# POV.net
KiCad netlist of a schematic drawn in EAGLE
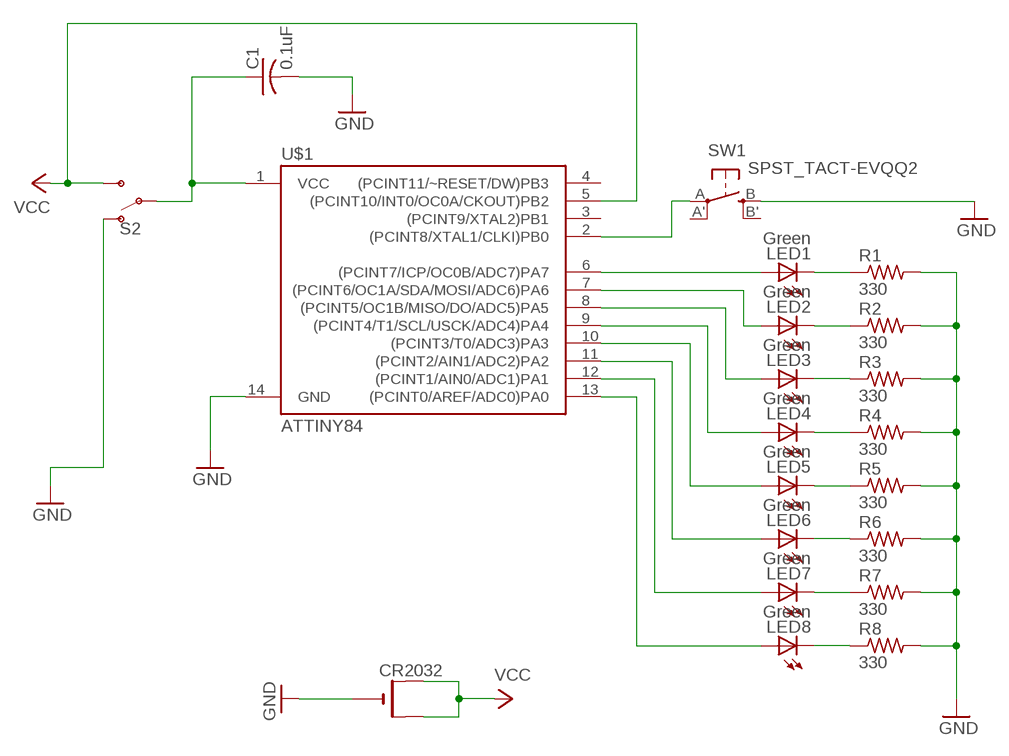
[diagram p0: schematic, sheet 1]

(export (version "E")
  (design (tool "Eeschema 10.0.6"))
  (components
    (comp (ref "C1")
      (value "0.1uF")
      (footprint "eagle-import:C0805")
      (libsource (lib "eagle-import") (part "C-USC0805"))
    )
    (comp (ref "CR2032")
      (value "CR2032SMT")
      (footprint "eagle-import:CR2032-SMD")
      (libsource (lib "eagle-import") (part "CR2032SMT"))
    )
    (comp (ref "LED1")
      (value "Green")
      (footprint "eagle-import:CHIP-LED0805")
      (libsource (lib "eagle-import") (part "LEDCHIP-LED0805"))
    )
    (comp (ref "LED2")
      (value "Green")
      (footprint "eagle-import:CHIP-LED0805")
      (libsource (lib "eagle-import") (part "LEDCHIP-LED0805"))
    )
    (comp (ref "LED3")
      (value "Green")
      (footprint "eagle-import:CHIP-LED0805")
      (libsource (lib "eagle-import") (part "LEDCHIP-LED0805"))
    )
    (comp (ref "LED4")
      (value "Green")
      (footprint "eagle-import:CHIP-LED0805")
      (libsource (lib "eagle-import") (part "LEDCHIP-LED0805"))
    )
    (comp (ref "LED5")
      (value "Green")
      (footprint "eagle-import:CHIP-LED0805")
      (libsource (lib "eagle-import") (part "LEDCHIP-LED0805"))
    )
    (comp (ref "LED6")
      (value "Green")
      (footprint "eagle-import:CHIP-LED0805")
      (libsource (lib "eagle-import") (part "LEDCHIP-LED0805"))
    )
    (comp (ref "LED7")
      (value "Green")
      (footprint "eagle-import:CHIP-LED0805")
      (libsource (lib "eagle-import") (part "LEDCHIP-LED0805"))
    )
    (comp (ref "LED8")
      (value "Green")
      (footprint "eagle-import:CHIP-LED0805")
      (libsource (lib "eagle-import") (part "LEDCHIP-LED0805"))
    )
    (comp (ref "R1")
      (value "330")
      (footprint "eagle-import:M0805")
      (libsource (lib "eagle-import") (part "R-US_M0805"))
    )
    (comp (ref "R2")
      (value "330")
      (footprint "eagle-import:M0805")
      (libsource (lib "eagle-import") (part "R-US_M0805"))
    )
    (comp (ref "R3")
      (value "330")
      (footprint "eagle-import:M0805")
      (libsource (lib "eagle-import") (part "R-US_M0805"))
    )
    (comp (ref "R4")
      (value "330")
      (footprint "eagle-import:M0805")
      (libsource (lib "eagle-import") (part "R-US_M0805"))
    )
    (comp (ref "R5")
      (value "330")
      (footprint "eagle-import:M0805")
      (libsource (lib "eagle-import") (part "R-US_M0805"))
    )
    (comp (ref "R6")
      (value "330")
      (footprint "eagle-import:M0805")
      (libsource (lib "eagle-import") (part "R-US_M0805"))
    )
    (comp (ref "R7")
      (value "330")
      (footprint "eagle-import:M0805")
      (libsource (lib "eagle-import") (part "R-US_M0805"))
    )
    (comp (ref "R8")
      (value "330")
      (footprint "eagle-import:M0805")
      (libsource (lib "eagle-import") (part "R-US_M0805"))
    )
    (comp (ref "S2")
      (value "SWITCH-SPDT-SMD-AYZ0202")
      (footprint "eagle-import:SWITCH_DPDT_SMD_AYZ0202")
      (libsource (lib "eagle-import") (part "SWITCH-SPDT-SMD-AYZ0202"))
    )
    (comp (ref "SW1")
      (value "SPST_TACT-EVQQ2")
      (footprint "eagle-import:EVQ-Q2")
      (libsource (lib "eagle-import") (part "SPST_TACT-EVQQ2"))
    )
    (comp (ref "U$1")
      (value "ATTINY84")
      (footprint "eagle-import:SO14")
      (libsource (lib "eagle-import") (part "ATTINY84"))
    )
  )
  (nets
    (net (code "1") (name "GND") (class "Default")
      (node (ref "C1") (pin "2") (pinfunction "2_2") (pintype "passive"))
      (node (ref "CR2032") (pin "-") (pinfunction "-_-") (pintype "passive"))
      (node (ref "R1") (pin "2") (pinfunction "2_2") (pintype "passive"))
      (node (ref "R2") (pin "2") (pinfunction "2_2") (pintype "passive"))
      (node (ref "R3") (pin "2") (pinfunction "2_2") (pintype "passive"))
      (node (ref "R4") (pin "2") (pinfunction "2_2") (pintype "passive"))
      (node (ref "R5") (pin "2") (pinfunction "2_2") (pintype "passive"))
      (node (ref "R6") (pin "2") (pinfunction "2_2") (pintype "passive"))
      (node (ref "R7") (pin "2") (pinfunction "2_2") (pintype "passive"))
      (node (ref "R8") (pin "2") (pinfunction "2_2") (pintype "passive"))
      (node (ref "S2") (pin "1") (pinfunction "O_1") (pintype "passive"))
      (node (ref "SW1") (pin "B") (pinfunction "S_B") (pintype "passive"))
      (node (ref "U$1") (pin "14") (pinfunction "GND_14") (pintype "bidirectional"))
    )
    (net (code "2") (name "Net-(LED1-PadC)") (class "Default")
      (node (ref "LED1") (pin "C") (pinfunction "C_C") (pintype "passive"))
      (node (ref "R1") (pin "1") (pinfunction "1_1") (pintype "passive"))
    )
    (net (code "3") (name "Net-(LED2-PadC)") (class "Default")
      (node (ref "LED2") (pin "C") (pinfunction "C_C") (pintype "passive"))
      (node (ref "R2") (pin "1") (pinfunction "1_1") (pintype "passive"))
    )
    (net (code "4") (name "Net-(LED3-PadC)") (class "Default")
      (node (ref "LED3") (pin "C") (pinfunction "C_C") (pintype "passive"))
      (node (ref "R3") (pin "1") (pinfunction "1_1") (pintype "passive"))
    )
    (net (code "5") (name "Net-(LED4-PadC)") (class "Default")
      (node (ref "LED4") (pin "C") (pinfunction "C_C") (pintype "passive"))
      (node (ref "R4") (pin "1") (pinfunction "1_1") (pintype "passive"))
    )
    (net (code "6") (name "Net-(LED5-PadC)") (class "Default")
      (node (ref "LED5") (pin "C") (pinfunction "C_C") (pintype "passive"))
      (node (ref "R5") (pin "1") (pinfunction "1_1") (pintype "passive"))
    )
    (net (code "7") (name "Net-(LED6-PadC)") (class "Default")
      (node (ref "LED6") (pin "C") (pinfunction "C_C") (pintype "passive"))
      (node (ref "R6") (pin "1") (pinfunction "1_1") (pintype "passive"))
    )
    (net (code "8") (name "Net-(LED7-PadC)") (class "Default")
      (node (ref "LED7") (pin "C") (pinfunction "C_C") (pintype "passive"))
      (node (ref "R7") (pin "1") (pinfunction "1_1") (pintype "passive"))
    )
    (net (code "9") (name "Net-(LED8-PadC)") (class "Default")
      (node (ref "LED8") (pin "C") (pinfunction "C_C") (pintype "passive"))
      (node (ref "R8") (pin "1") (pinfunction "1_1") (pintype "passive"))
    )
    (net (code "10") (name "Net-(S2-P)") (class "Default")
      (node (ref "C1") (pin "1") (pinfunction "1_1") (pintype "passive"))
      (node (ref "S2") (pin "2") (pinfunction "P_2") (pintype "passive"))
      (node (ref "U$1") (pin "1") (pinfunction "VCC_1") (pintype "bidirectional"))
    )
    (net (code "11") (name "Net-(SW1-P)") (class "Default")
      (node (ref "SW1") (pin "A") (pinfunction "P_A") (pintype "passive"))
      (node (ref "U$1") (pin "2") (pinfunction "(PCINT8/XTAL1/CLKI)PB0_2") (pintype "bidirectional"))
    )
    (net (code "12") (name "Net-(U$1-(PCINT0{slash}AREF{slash}ADC0)PA0)") (class "Default")
      (node (ref "LED8") (pin "A") (pinfunction "A_A") (pintype "passive"))
      (node (ref "U$1") (pin "13") (pinfunction "(PCINT0/AREF/ADC0)PA0_13") (pintype "bidirectional"))
    )
    (net (code "13") (name "Net-(U$1-(PCINT1{slash}AIN0{slash}ADC1)PA1)") (class "Default")
      (node (ref "LED7") (pin "A") (pinfunction "A_A") (pintype "passive"))
      (node (ref "U$1") (pin "12") (pinfunction "(PCINT1/AIN0/ADC1)PA1_12") (pintype "bidirectional"))
    )
    (net (code "14") (name "Net-(U$1-(PCINT2{slash}AIN1{slash}ADC2)PA2)") (class "Default")
      (node (ref "LED6") (pin "A") (pinfunction "A_A") (pintype "passive"))
      (node (ref "U$1") (pin "11") (pinfunction "(PCINT2/AIN1/ADC2)PA2_11") (pintype "bidirectional"))
    )
    (net (code "15") (name "Net-(U$1-(PCINT3{slash}T0{slash}ADC3)PA3)") (class "Default")
      (node (ref "LED5") (pin "A") (pinfunction "A_A") (pintype "passive"))
      (node (ref "U$1") (pin "10") (pinfunction "(PCINT3/T0/ADC3)PA3_10") (pintype "bidirectional"))
    )
    (net (code "16") (name "Net-(U$1-(PCINT4{slash}T1{slash}SCL{slash}USCK{slash}ADC4)PA4)") (class "Default")
      (node (ref "LED4") (pin "A") (pinfunction "A_A") (pintype "passive"))
      (node (ref "U$1") (pin "9") (pinfunction "(PCINT4/T1/SCL/USCK/ADC4)PA4_9") (pintype "bidirectional"))
    )
    (net (code "17") (name "Net-(U$1-(PCINT5{slash}OC1B{slash}MISO{slash}DO{slash}ADC5)PA5)") (class "Default")
      (node (ref "LED3") (pin "A") (pinfunction "A_A") (pintype "passive"))
      (node (ref "U$1") (pin "8") (pinfunction "(PCINT5/OC1B/MISO/DO/ADC5)PA5_8") (pintype "bidirectional"))
    )
    (net (code "18") (name "Net-(U$1-(PCINT6{slash}OC1A{slash}SDA{slash}MOSI{slash}ADC6)PA6)") (class "Default")
      (node (ref "LED2") (pin "A") (pinfunction "A_A") (pintype "passive"))
      (node (ref "U$1") (pin "7") (pinfunction "(PCINT6/OC1A/SDA/MOSI/ADC6)PA6_7") (pintype "bidirectional"))
    )
    (net (code "19") (name "Net-(U$1-(PCINT7{slash}ICP{slash}OC0B{slash}ADC7)PA7)") (class "Default")
      (node (ref "LED1") (pin "A") (pinfunction "A_A") (pintype "passive"))
      (node (ref "U$1") (pin "6") (pinfunction "(PCINT7/ICP/OC0B/ADC7)PA7_6") (pintype "bidirectional"))
    )
    (net (code "20") (name "VCC") (class "Default")
      (node (ref "CR2032") (pin "+$1") (pinfunction "+_+$1") (pintype "passive"))
      (node (ref "CR2032") (pin "+$2") (pinfunction "+1_+$2") (pintype "passive"))
      (node (ref "S2") (pin "3") (pinfunction "S_3") (pintype "passive"))
      (node (ref "U$1") (pin "5") (pinfunction "(PCINT10/INT0/OC0A/CKOUT)PB2_5") (pintype "bidirectional"))
    )
    (net (code "21") (name "unconnected-(SW1-P1-PadA')") (class "Default")
      (node (ref "SW1") (pin "A'") (pinfunction "P1_A'") (pintype "passive"))
    )
    (net (code "22") (name "unconnected-(SW1-S1-PadB')") (class "Default")
      (node (ref "SW1") (pin "B'") (pinfunction "S1_B'") (pintype "passive"))
    )
    (net (code "23") (name "unconnected-(U$1-(PCINT9{slash}XTAL2)PB1-Pad3)") (class "Default")
      (node (ref "U$1") (pin "3") (pinfunction "(PCINT9/XTAL2)PB1_3") (pintype "bidirectional"))
    )
    (net (code "24") (name "unconnected-(U$1-(PCINT11{slash}~{RESET{slash}DW})PB3-Pad4)") (class "Default")
      (node (ref "U$1") (pin "4") (pinfunction "(PCINT11/~{RESET/DW})PB3_4") (pintype "bidirectional"))
    )
  )
)
